# D-ad_SIL-DIL.net
KiCad netlist of a schematic drawn in EAGLE
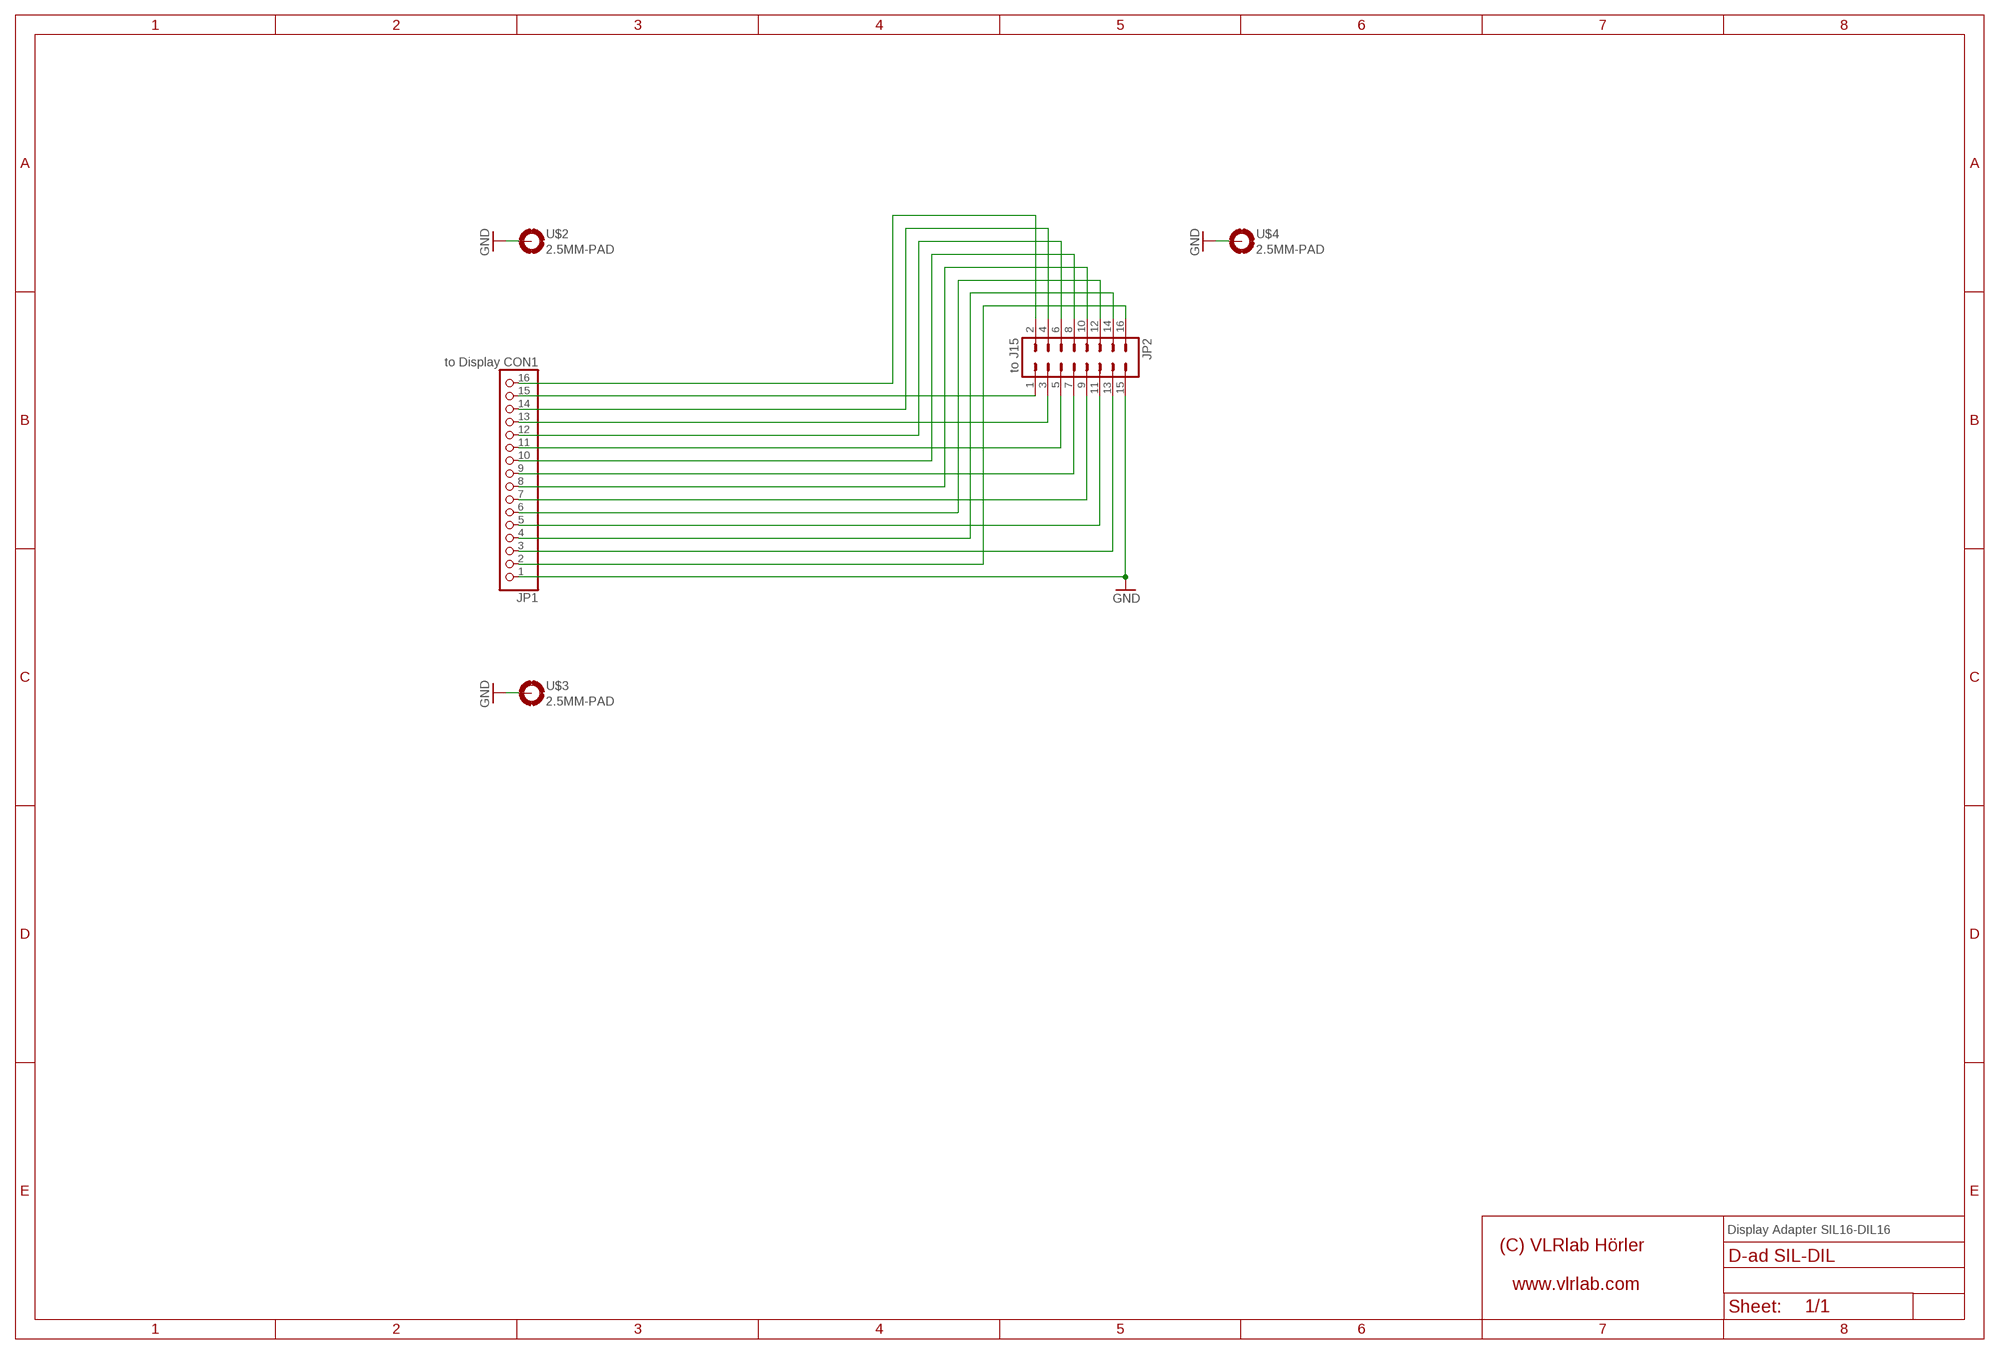
[diagram p0: schematic, sheet 1]

(export (version "E")
  (design (tool "Eeschema 10.0.6"))
  (components
    (comp (ref "JP1")
      (value "to Display CON1")
      (footprint "eagle-import:1X16")
      (libsource (lib "eagle-import") (part "PINHD-1X16"))
    )
    (comp (ref "JP2")
      (value "to J15")
      (footprint "eagle-import:ML16")
      (libsource (lib "eagle-import") (part "ML16"))
    )
    (comp (ref "U$2")
      (value "2.5MM-PAD")
      (footprint "eagle-import:2.5MM-PAD")
      (libsource (lib "eagle-import") (part "2.5MM-PAD"))
    )
    (comp (ref "U$3")
      (value "2.5MM-PAD")
      (footprint "eagle-import:2.5MM-PAD")
      (libsource (lib "eagle-import") (part "2.5MM-PAD"))
    )
    (comp (ref "U$4")
      (value "2.5MM-PAD")
      (footprint "eagle-import:2.5MM-PAD")
      (libsource (lib "eagle-import") (part "2.5MM-PAD"))
    )
  )
  (nets
    (net (code "1") (name "GND") (class "Default")
      (node (ref "JP1") (pin "1") (pinfunction "1_1") (pintype "passive"))
      (node (ref "JP2") (pin "15") (pinfunction "15_15") (pintype "passive"))
      (node (ref "U$2") (pin "B3,2") (pinfunction "MOUNT_B3,2") (pintype "passive"))
      (node (ref "U$3") (pin "B3,2") (pinfunction "MOUNT_B3,2") (pintype "passive"))
      (node (ref "U$4") (pin "B3,2") (pinfunction "MOUNT_B3,2") (pintype "passive"))
    )
    (net (code "2") (name "Net-(JP1-Pad2)") (class "Default")
      (node (ref "JP1") (pin "2") (pinfunction "2_2") (pintype "passive"))
      (node (ref "JP2") (pin "16") (pinfunction "16_16") (pintype "passive"))
    )
    (net (code "3") (name "Net-(JP1-Pad3)") (class "Default")
      (node (ref "JP1") (pin "3") (pinfunction "3_3") (pintype "passive"))
      (node (ref "JP2") (pin "13") (pinfunction "13_13") (pintype "passive"))
    )
    (net (code "4") (name "Net-(JP1-Pad4)") (class "Default")
      (node (ref "JP1") (pin "4") (pinfunction "4_4") (pintype "passive"))
      (node (ref "JP2") (pin "14") (pinfunction "14_14") (pintype "passive"))
    )
    (net (code "5") (name "Net-(JP1-Pad5)") (class "Default")
      (node (ref "JP1") (pin "5") (pinfunction "5_5") (pintype "passive"))
      (node (ref "JP2") (pin "11") (pinfunction "11_11") (pintype "passive"))
    )
    (net (code "6") (name "Net-(JP1-Pad6)") (class "Default")
      (node (ref "JP1") (pin "6") (pinfunction "6_6") (pintype "passive"))
      (node (ref "JP2") (pin "12") (pinfunction "12_12") (pintype "passive"))
    )
    (net (code "7") (name "Net-(JP1-Pad7)") (class "Default")
      (node (ref "JP1") (pin "7") (pinfunction "7_7") (pintype "passive"))
      (node (ref "JP2") (pin "9") (pinfunction "9_9") (pintype "passive"))
    )
    (net (code "8") (name "Net-(JP1-Pad8)") (class "Default")
      (node (ref "JP1") (pin "8") (pinfunction "8_8") (pintype "passive"))
      (node (ref "JP2") (pin "10") (pinfunction "10_10") (pintype "passive"))
    )
    (net (code "9") (name "Net-(JP1-Pad9)") (class "Default")
      (node (ref "JP1") (pin "9") (pinfunction "9_9") (pintype "passive"))
      (node (ref "JP2") (pin "7") (pinfunction "7_7") (pintype "passive"))
    )
    (net (code "10") (name "Net-(JP1-Pad10)") (class "Default")
      (node (ref "JP1") (pin "10") (pinfunction "10_10") (pintype "passive"))
      (node (ref "JP2") (pin "8") (pinfunction "8_8") (pintype "passive"))
    )
    (net (code "11") (name "Net-(JP1-Pad11)") (class "Default")
      (node (ref "JP1") (pin "11") (pinfunction "11_11") (pintype "passive"))
      (node (ref "JP2") (pin "5") (pinfunction "5_5") (pintype "passive"))
    )
    (net (code "12") (name "Net-(JP1-Pad12)") (class "Default")
      (node (ref "JP1") (pin "12") (pinfunction "12_12") (pintype "passive"))
      (node (ref "JP2") (pin "6") (pinfunction "6_6") (pintype "passive"))
    )
    (net (code "13") (name "Net-(JP1-Pad13)") (class "Default")
      (node (ref "JP1") (pin "13") (pinfunction "13_13") (pintype "passive"))
      (node (ref "JP2") (pin "3") (pinfunction "3_3") (pintype "passive"))
    )
    (net (code "14") (name "Net-(JP1-Pad14)") (class "Default")
      (node (ref "JP1") (pin "14") (pinfunction "14_14") (pintype "passive"))
      (node (ref "JP2") (pin "4") (pinfunction "4_4") (pintype "passive"))
    )
    (net (code "15") (name "Net-(JP1-Pad15)") (class "Default")
      (node (ref "JP1") (pin "15") (pinfunction "15_15") (pintype "passive"))
      (node (ref "JP2") (pin "1") (pinfunction "1_1") (pintype "passive"))
    )
    (net (code "16") (name "Net-(JP1-Pad16)") (class "Default")
      (node (ref "JP1") (pin "16") (pinfunction "16_16") (pintype "passive"))
      (node (ref "JP2") (pin "2") (pinfunction "2_2") (pintype "passive"))
    )
  )
)
